# LPCB224_-_PSU.net
KiCad netlist of a schematic drawn in Altium Designer
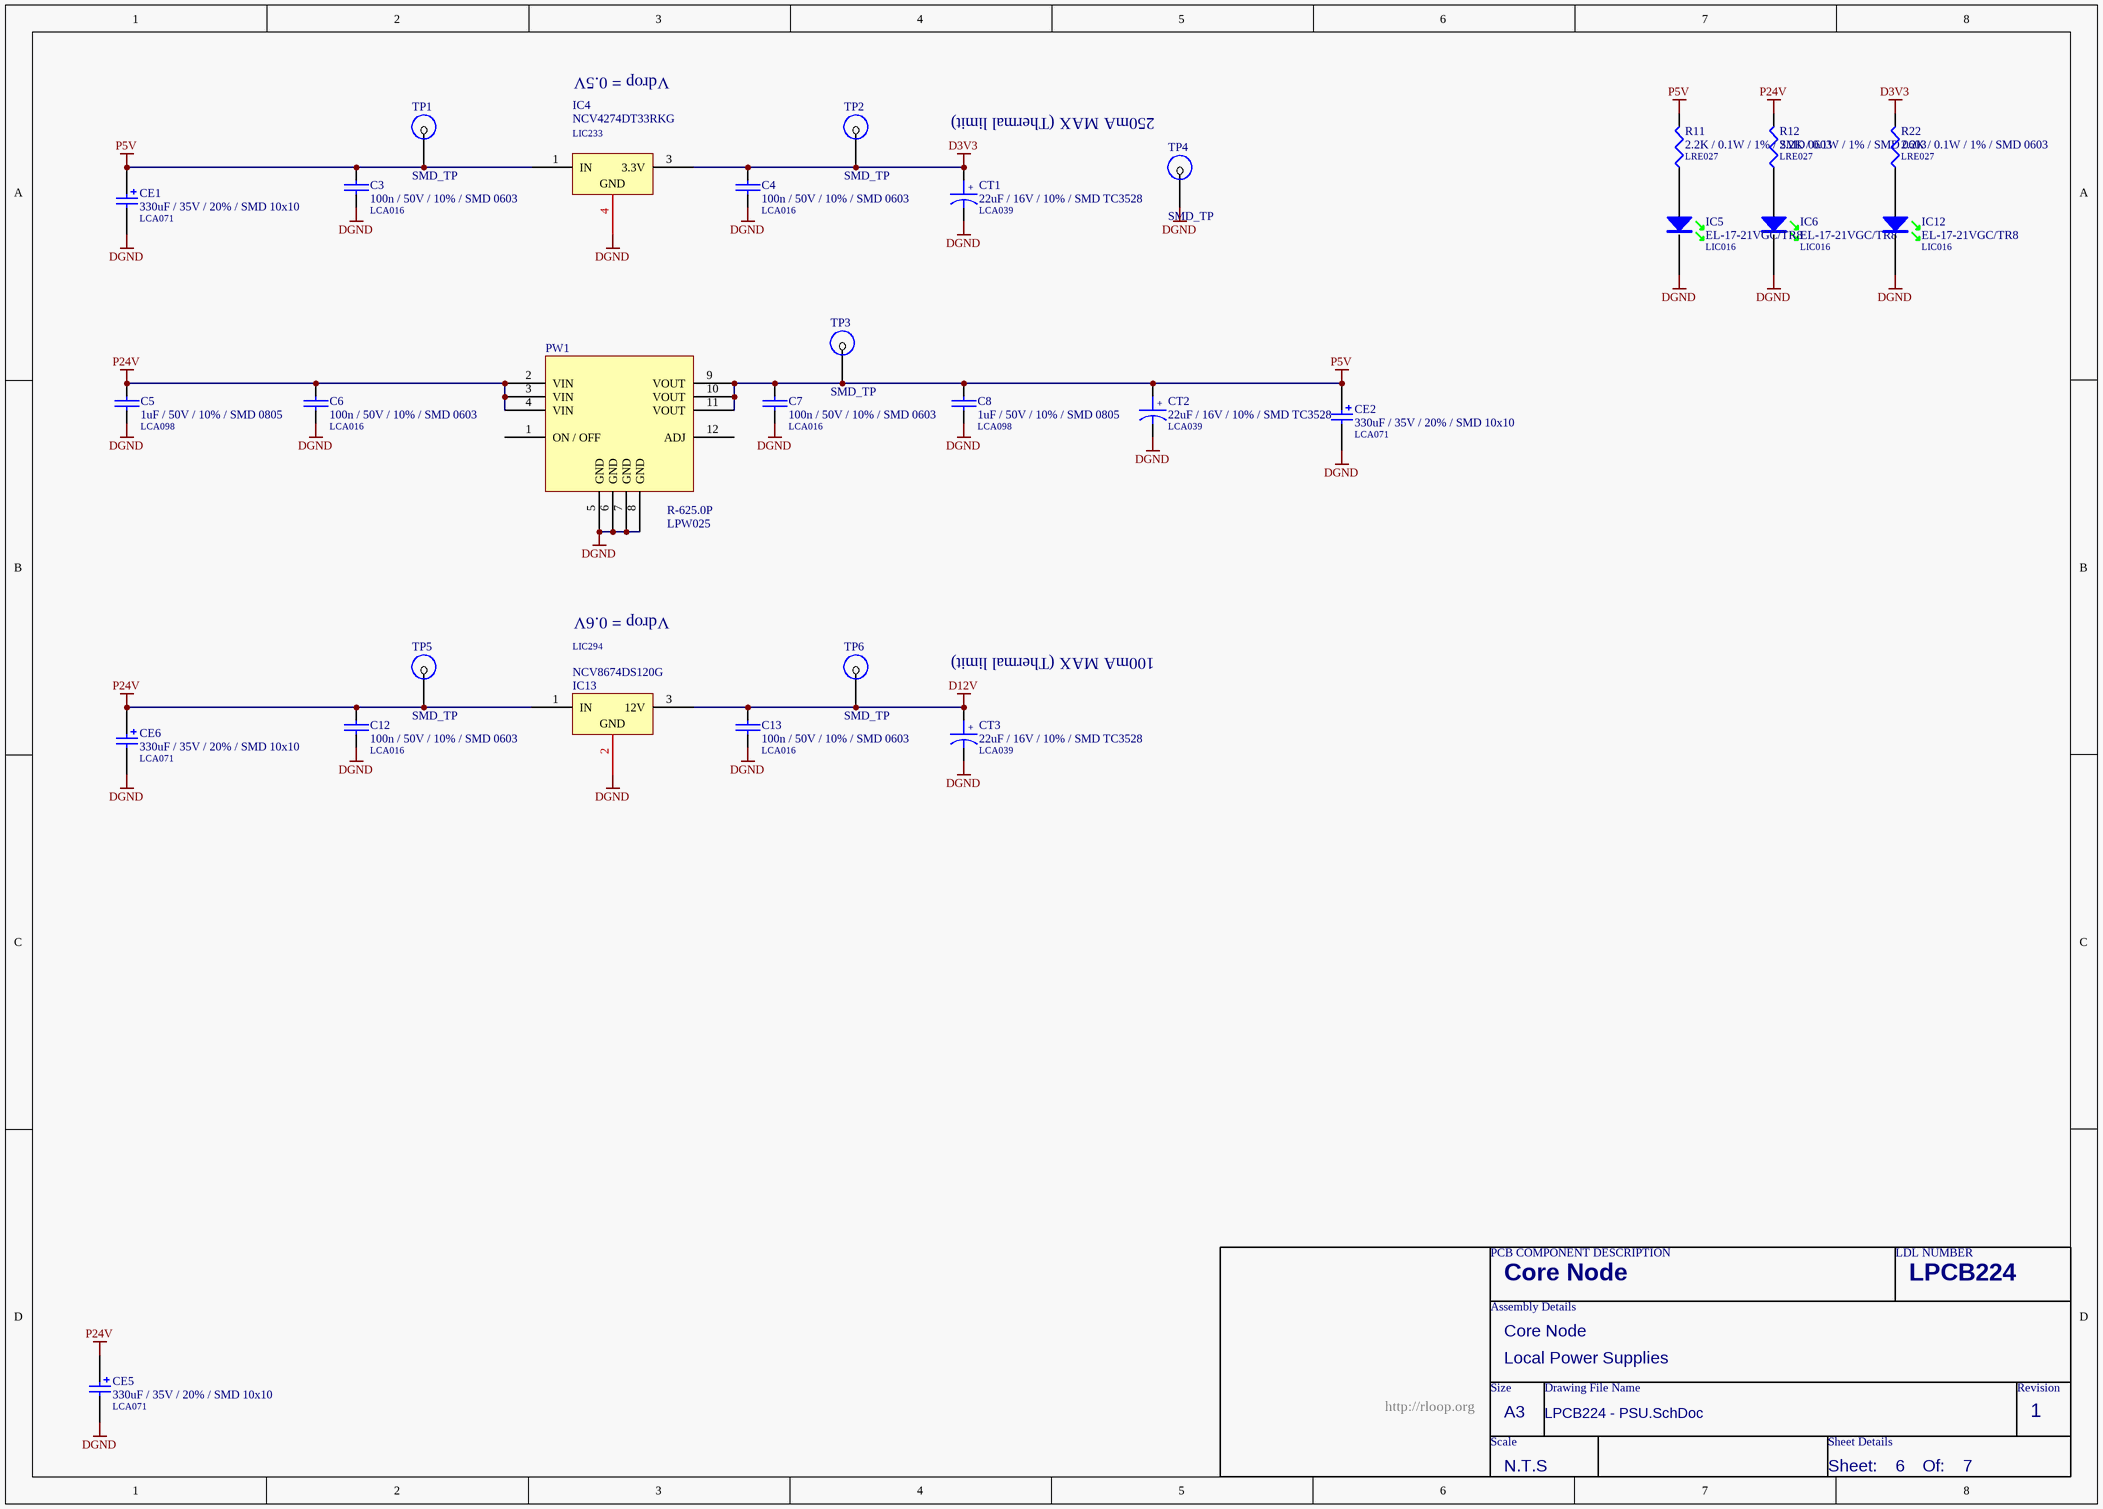
[diagram p0: LPCB224 - PSU.SchDoc]

(export (version "E")
  (design (tool "Eeschema 10.0.6"))
  (components
    (comp (ref "C3")
      (value "100n / 50V / 10% / SMD 0603")
      (footprint "LFP011__CC1608-0603-IPC7351_B")
      (description "Capacitor, Ceramic Chip, 100nF (0.1uF), 50V, 5%, SMD 0603 [LCA016]")
      (fields (field (name "LDL_NUMBER") "LCA016"))
      (libsource (lib "LDL_Capacitors") (part "100n / 50V / 10% / SMD 0603"))
    )
    (comp (ref "C4")
      (value "100n / 50V / 10% / SMD 0603")
      (footprint "LFP011__CC1608-0603-IPC7351_B")
      (description "Capacitor, Ceramic Chip, 100nF (0.1uF), 50V, 5%, SMD 0603 [LCA016]")
      (fields (field (name "LDL_NUMBER") "LCA016"))
      (libsource (lib "LDL_Capacitors") (part "100n / 50V / 10% / SMD 0603"))
    )
    (comp (ref "C5")
      (value "1uF / 50V / 10% / SMD 0805")
      (footprint "LFP010__CC2012-0805-IPC7351_B")
      (description "Capacitor, Ceramic Chip, 1uF, 50V, SMD 0805 [LCA098]")
      (fields (field (name "LDL_NUMBER") "LCA098"))
      (libsource (lib "LDL_Capacitors") (part "1uF / 50V / 10% / SMD 0805"))
    )
    (comp (ref "C6")
      (value "100n / 50V / 10% / SMD 0603")
      (footprint "LFP011__CC1608-0603-IPC7351_B")
      (description "Capacitor, Ceramic Chip, 100nF (0.1uF), 50V, 5%, SMD 0603 [LCA016]")
      (fields (field (name "LDL_NUMBER") "LCA016"))
      (libsource (lib "LDL_Capacitors") (part "100n / 50V / 10% / SMD 0603"))
    )
    (comp (ref "C7")
      (value "100n / 50V / 10% / SMD 0603")
      (footprint "LFP011__CC1608-0603-IPC7351_B")
      (description "Capacitor, Ceramic Chip, 100nF (0.1uF), 50V, 5%, SMD 0603 [LCA016]")
      (fields (field (name "LDL_NUMBER") "LCA016"))
      (libsource (lib "LDL_Capacitors") (part "100n / 50V / 10% / SMD 0603"))
    )
    (comp (ref "C8")
      (value "1uF / 50V / 10% / SMD 0805")
      (footprint "LFP010__CC2012-0805-IPC7351_B")
      (description "Capacitor, Ceramic Chip, 1uF, 50V, SMD 0805 [LCA098]")
      (fields (field (name "LDL_NUMBER") "LCA098"))
      (libsource (lib "LDL_Capacitors") (part "1uF / 50V / 10% / SMD 0805"))
    )
    (comp (ref "C12")
      (value "100n / 50V / 10% / SMD 0603")
      (footprint "LFP011__CC1608-0603-IPC7351_B")
      (description "Capacitor, Ceramic Chip, 100nF (0.1uF), 50V, 5%, SMD 0603 [LCA016]")
      (fields (field (name "LDL_NUMBER") "LCA016"))
      (libsource (lib "LDL_Capacitors") (part "100n / 50V / 10% / SMD 0603"))
    )
    (comp (ref "C13")
      (value "100n / 50V / 10% / SMD 0603")
      (footprint "LFP011__CC1608-0603-IPC7351_B")
      (description "Capacitor, Ceramic Chip, 100nF (0.1uF), 50V, 5%, SMD 0603 [LCA016]")
      (fields (field (name "LDL_NUMBER") "LCA016"))
      (libsource (lib "LDL_Capacitors") (part "100n / 50V / 10% / SMD 0603"))
    )
    (comp (ref "CE1")
      (value "330uF / 35V / 20% / SMD 10x10")
      (footprint "LFP041__NICHICON_WT_10X10")
      (description "Capacitor, Aluminum Electrolytic, 330uF, 35V, 20%, SMD (10mm x 10mm) [LCA071]")
      (fields (field (name "LDL_NUMBER") "LCA071"))
      (libsource (lib "LDL_Capacitors") (part "330uF / 35V / 20% / SMD 10x10"))
    )
    (comp (ref "CE2")
      (value "330uF / 35V / 20% / SMD 10x10")
      (footprint "LFP041__NICHICON_WT_10X10")
      (description "Capacitor, Aluminum Electrolytic, 330uF, 35V, 20%, SMD (10mm x 10mm) [LCA071]")
      (fields (field (name "LDL_NUMBER") "LCA071"))
      (libsource (lib "LDL_Capacitors") (part "330uF / 35V / 20% / SMD 10x10"))
    )
    (comp (ref "CE5")
      (value "330uF / 35V / 20% / SMD 10x10")
      (footprint "LFP041__NICHICON_WT_10X10")
      (description "Capacitor, Aluminum Electrolytic, 330uF, 35V, 20%, SMD (10mm x 10mm) [LCA071]")
      (fields (field (name "LDL_NUMBER") "LCA071"))
      (libsource (lib "LDL_Capacitors") (part "330uF / 35V / 20% / SMD 10x10"))
    )
    (comp (ref "CE6")
      (value "330uF / 35V / 20% / SMD 10x10")
      (footprint "LFP041__NICHICON_WT_10X10")
      (description "Capacitor, Aluminum Electrolytic, 330uF, 35V, 20%, SMD (10mm x 10mm) [LCA071]")
      (fields (field (name "LDL_NUMBER") "LCA071"))
      (libsource (lib "LDL_Capacitors") (part "330uF / 35V / 20% / SMD 10x10"))
    )
    (comp (ref "CT1")
      (value "22uF / 16V / 10% / SMD TC3528")
      (footprint "LFP018__TC3528")
      (description "Capacitor, Tantalum, 22uF, 16V, 10%, SMD TC3528 (BCASE) [LCA039]")
      (fields (field (name "LDL_NUMBER") "LCA039"))
      (libsource (lib "LDL_Capacitors") (part "22uF / 16V / 10% / SMD TC3528"))
    )
    (comp (ref "CT2")
      (value "22uF / 16V / 10% / SMD TC3528")
      (footprint "LFP018__TC3528")
      (description "Capacitor, Tantalum, 22uF, 16V, 10%, SMD TC3528 (BCASE) [LCA039]")
      (fields (field (name "LDL_NUMBER") "LCA039"))
      (libsource (lib "LDL_Capacitors") (part "22uF / 16V / 10% / SMD TC3528"))
    )
    (comp (ref "CT3")
      (value "22uF / 16V / 10% / SMD TC3528")
      (footprint "LFP018__TC3528")
      (description "Capacitor, Tantalum, 22uF, 16V, 10%, SMD TC3528 (BCASE) [LCA039]")
      (fields (field (name "LDL_NUMBER") "LCA039"))
      (libsource (lib "LDL_Capacitors") (part "22uF / 16V / 10% / SMD TC3528"))
    )
    (comp (ref "IC4")
      (value "NCV4274DT33RKG")
      (footprint "LFP019__369A-13")
      (description "IC, Voltage Regulator, 400mA, 3.3V LDO, SMD DPAK [LIC233]")
      (fields (field (name "LDL_NUMBER") "LIC233"))
      (libsource (lib "LDL_Semiconductors") (part "NCV4274DT33RKG"))
    )
    (comp (ref "IC5")
      (value "EL-17-21VGC/TR8")
      (footprint "CR2012-0805-LED")
      (description "LED, SMD, 0805 Green [LIC016]")
      (fields (field (name "LDL_NUMBER") "LIC016"))
      (libsource (lib "LDL_Semiconductors") (part "EL-17-21VGC/TR8"))
    )
    (comp (ref "IC6")
      (value "EL-17-21VGC/TR8")
      (footprint "CR2012-0805-LED")
      (description "LED, SMD, 0805 Green [LIC016]")
      (fields (field (name "LDL_NUMBER") "LIC016"))
      (libsource (lib "LDL_Semiconductors") (part "EL-17-21VGC/TR8"))
    )
    (comp (ref "IC12")
      (value "EL-17-21VGC/TR8")
      (footprint "CR2012-0805-LED")
      (description "LED, SMD, 0805 Green [LIC016]")
      (fields (field (name "LDL_NUMBER") "LIC016"))
      (libsource (lib "LDL_Semiconductors") (part "EL-17-21VGC/TR8"))
    )
    (comp (ref "IC13")
      (value "NCV8674DS120G")
      (footprint "LFP082__D2PAK")
      (description "IC, Voltage Regulator, 0.35A, 12V, SMD D2PAK [LIC294]")
      (fields (field (name "LDL_NUMBER") "LIC294"))
      (libsource (lib "LDL_Semiconductors") (part "NCV8674DS120G"))
    )
    (comp (ref "PW1")
      (value "R-625.0P")
      (footprint "R-625.0P")
      (description "Non Isolated DC/DC Module")
      (fields (field (name "LDL_NUMBER") "LPW025"))
      (libsource (lib "LDL_Power") (part "R-625.0P"))
    )
    (comp (ref "R11")
      (value "2.2K / 0.1W / 1% / SMD 0603")
      (footprint "LFP020__CR1608-0603-IPC7351_B")
      (description "Resistor, Ceramic Chip, 2.2K, 0.1W, 1%, SMD 0603 [LRE027]")
      (fields (field (name "LDL_NUMBER") "LRE027"))
      (libsource (lib "LDL_Resistors") (part "2.2K / 0.1W / 1% / SMD 0603"))
    )
    (comp (ref "R12")
      (value "2.2K / 0.1W / 1% / SMD 0603")
      (footprint "LFP020__CR1608-0603-IPC7351_B")
      (description "Resistor, Ceramic Chip, 2.2K, 0.1W, 1%, SMD 0603 [LRE027]")
      (fields (field (name "LDL_NUMBER") "LRE027"))
      (libsource (lib "LDL_Resistors") (part "2.2K / 0.1W / 1% / SMD 0603"))
    )
    (comp (ref "R22")
      (value "2.2K / 0.1W / 1% / SMD 0603")
      (footprint "LFP020__CR1608-0603-IPC7351_B")
      (description "Resistor, Ceramic Chip, 2.2K, 0.1W, 1%, SMD 0603 [LRE027]")
      (fields (field (name "LDL_NUMBER") "LRE027"))
      (libsource (lib "LDL_Resistors") (part "2.2K / 0.1W / 1% / SMD 0603"))
    )
    (comp (ref "TP1")
      (value "SMD_TP")
      (footprint "SMD-TP")
      (description "SMD Test Point")
      (libsource (lib "LDL_Connectors") (part "SMD_TP"))
    )
    (comp (ref "TP2")
      (value "SMD_TP")
      (footprint "SMD-TP")
      (description "SMD Test Point")
      (libsource (lib "LDL_Connectors") (part "SMD_TP"))
    )
    (comp (ref "TP3")
      (value "SMD_TP")
      (footprint "SMD-TP")
      (description "SMD Test Point")
      (libsource (lib "LDL_Connectors") (part "SMD_TP"))
    )
    (comp (ref "TP4")
      (value "SMD_TP")
      (footprint "SMD-TP")
      (description "SMD Test Point")
      (libsource (lib "LDL_Connectors") (part "SMD_TP"))
    )
    (comp (ref "TP5")
      (value "SMD_TP")
      (footprint "SMD-TP")
      (description "SMD Test Point")
      (libsource (lib "LDL_Connectors") (part "SMD_TP"))
    )
    (comp (ref "TP6")
      (value "SMD_TP")
      (footprint "SMD-TP")
      (description "SMD Test Point")
      (libsource (lib "LDL_Connectors") (part "SMD_TP"))
    )
  )
  (nets
    (net (code "1") (name "D3V3") (class "Default")
      (node (ref "C4") (pin "1") (pintype "passive"))
      (node (ref "CT1") (pin "1") (pinfunction "1_1") (pintype "passive"))
      (node (ref "IC4") (pin "3") (pinfunction "3.3V_3") (pintype "power_in"))
      (node (ref "R22") (pin "2") (pintype "passive"))
      (node (ref "TP2") (pin "1") (pintype "passive"))
    )
    (net (code "2") (name "D12V") (class "Default")
      (node (ref "C13") (pin "1") (pintype "passive"))
      (node (ref "CT3") (pin "1") (pinfunction "1_1") (pintype "passive"))
      (node (ref "IC13") (pin "3") (pinfunction "12V_3") (pintype "power_in"))
      (node (ref "TP6") (pin "1") (pintype "passive"))
    )
    (net (code "3") (name "DGND") (class "Default")
      (node (ref "C12") (pin "2") (pintype "passive"))
      (node (ref "C13") (pin "2") (pintype "passive"))
      (node (ref "C3") (pin "2") (pintype "passive"))
      (node (ref "C4") (pin "2") (pintype "passive"))
      (node (ref "C5") (pin "2") (pintype "passive"))
      (node (ref "C6") (pin "2") (pintype "passive"))
      (node (ref "C7") (pin "2") (pintype "passive"))
      (node (ref "C8") (pin "2") (pintype "passive"))
      (node (ref "CE1") (pin "2") (pinfunction "2_2") (pintype "passive"))
      (node (ref "CE2") (pin "2") (pinfunction "2_2") (pintype "passive"))
      (node (ref "CE5") (pin "2") (pinfunction "2_2") (pintype "passive"))
      (node (ref "CE6") (pin "2") (pinfunction "2_2") (pintype "passive"))
      (node (ref "CT1") (pin "2") (pinfunction "2_2") (pintype "passive"))
      (node (ref "CT2") (pin "2") (pinfunction "2_2") (pintype "passive"))
      (node (ref "CT3") (pin "2") (pinfunction "2_2") (pintype "passive"))
      (node (ref "IC12") (pin "K") (pintype "passive"))
      (node (ref "IC13") (pin "2") (pinfunction "GND_2") (pintype "power_in"))
      (node (ref "IC4") (pin "4") (pinfunction "GND_4") (pintype "power_in"))
      (node (ref "IC5") (pin "K") (pintype "passive"))
      (node (ref "IC6") (pin "K") (pintype "passive"))
      (node (ref "PW1") (pin "5") (pinfunction "GND_5") (pintype "power_in"))
      (node (ref "PW1") (pin "6") (pinfunction "GND_6") (pintype "power_in"))
      (node (ref "PW1") (pin "7") (pinfunction "GND_7") (pintype "power_in"))
      (node (ref "PW1") (pin "8") (pinfunction "GND_8") (pintype "power_in"))
      (node (ref "TP4") (pin "1") (pintype "passive"))
    )
    (net (code "4") (name "Net-(IC5-PadA)") (class "Default")
      (node (ref "IC5") (pin "A") (pintype "passive"))
      (node (ref "R11") (pin "1") (pintype "passive"))
    )
    (net (code "5") (name "Net-(IC6-PadA)") (class "Default")
      (node (ref "IC6") (pin "A") (pintype "passive"))
      (node (ref "R12") (pin "1") (pintype "passive"))
    )
    (net (code "6") (name "Net-(IC12-PadA)") (class "Default")
      (node (ref "IC12") (pin "A") (pintype "passive"))
      (node (ref "R22") (pin "1") (pintype "passive"))
    )
    (net (code "7") (name "P5V") (class "Default")
      (node (ref "C3") (pin "1") (pintype "passive"))
      (node (ref "C7") (pin "1") (pintype "passive"))
      (node (ref "C8") (pin "1") (pintype "passive"))
      (node (ref "CE1") (pin "1") (pinfunction "1_1") (pintype "passive"))
      (node (ref "CE2") (pin "1") (pinfunction "1_1") (pintype "passive"))
      (node (ref "CT2") (pin "1") (pinfunction "1_1") (pintype "passive"))
      (node (ref "IC4") (pin "1") (pinfunction "IN_1") (pintype "power_in"))
      (node (ref "PW1") (pin "10") (pinfunction "VOUT_10") (pintype "power_in"))
      (node (ref "PW1") (pin "11") (pinfunction "VOUT_11") (pintype "power_in"))
      (node (ref "PW1") (pin "9") (pinfunction "VOUT_9") (pintype "power_in"))
      (node (ref "R11") (pin "2") (pintype "passive"))
      (node (ref "TP1") (pin "1") (pintype "passive"))
      (node (ref "TP3") (pin "1") (pintype "passive"))
    )
    (net (code "8") (name "P24V") (class "Default")
      (node (ref "C12") (pin "1") (pintype "passive"))
      (node (ref "C5") (pin "1") (pintype "passive"))
      (node (ref "C6") (pin "1") (pintype "passive"))
      (node (ref "CE5") (pin "1") (pinfunction "1_1") (pintype "passive"))
      (node (ref "CE6") (pin "1") (pinfunction "1_1") (pintype "passive"))
      (node (ref "IC13") (pin "1") (pinfunction "IN_1") (pintype "power_in"))
      (node (ref "PW1") (pin "2") (pinfunction "VIN_2") (pintype "power_in"))
      (node (ref "PW1") (pin "3") (pinfunction "VIN_3") (pintype "power_in"))
      (node (ref "PW1") (pin "4") (pinfunction "VIN_4") (pintype "power_in"))
      (node (ref "R12") (pin "2") (pintype "passive"))
      (node (ref "TP5") (pin "1") (pintype "passive"))
    )
    (net (code "9") (name "unconnected-(PW1-ADJ-Pad12)") (class "Default")
      (node (ref "PW1") (pin "12") (pinfunction "ADJ_12") (pintype "passive"))
    )
    (net (code "10") (name "unconnected-(PW1-ON_{slash}_OFF-Pad1)") (class "Default")
      (node (ref "PW1") (pin "1") (pinfunction "ON_/_OFF_1") (pintype "passive"))
    )
  )
)
